# ArduBerry_V6_b.net
KiCad netlist of a schematic drawn in EAGLE
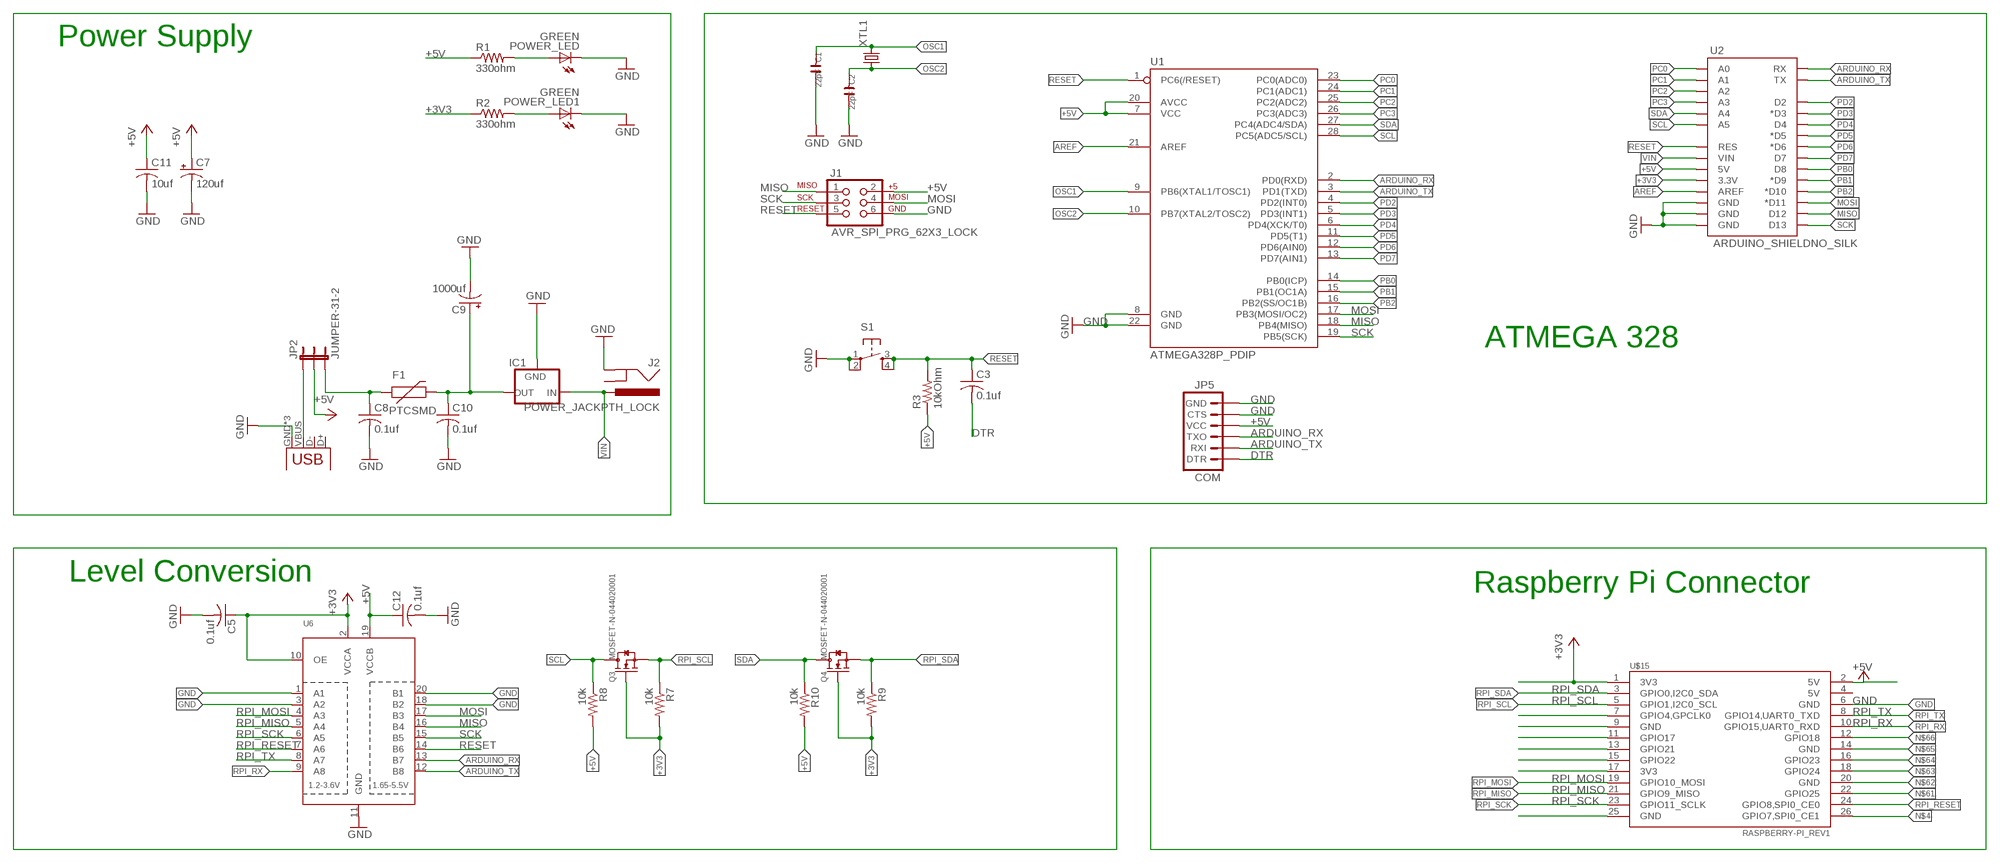
[diagram p0: schematic, sheet 1]

(export (version "E")
  (design (tool "Eeschema 10.0.6"))
  (components
    (comp (ref "C1")
      (value "22pF")
      (footprint "eagle-import:C0805")
      (libsource (lib "eagle-import") (part "C-0805"))
    )
    (comp (ref "C2")
      (value "22pF")
      (footprint "eagle-import:C0805")
      (libsource (lib "eagle-import") (part "C-0805"))
    )
    (comp (ref "C3")
      (value "0.1uf")
      (footprint "eagle-import:C0603")
      (libsource (lib "eagle-import") (part "resistor_C-USC0603"))
    )
    (comp (ref "C5")
      (value "0.1uf")
      (footprint "eagle-import:C0603")
      (libsource (lib "eagle-import") (part "resistor_C-USC0603"))
    )
    (comp (ref "C7")
      (value "120uf")
      (footprint "eagle-import:E2,5-6")
      (libsource (lib "eagle-import") (part "CPOL-USE2.5-6"))
    )
    (comp (ref "C8")
      (value "0.1uf")
      (footprint "eagle-import:C0603")
      (libsource (lib "eagle-import") (part "resistor_C-USC0603"))
    )
    (comp (ref "C9")
      (value "1000uf")
      (footprint "eagle-import:E3,5-10")
      (libsource (lib "eagle-import") (part "CPOL-USE3.5-10"))
    )
    (comp (ref "C10")
      (value "0.1uf")
      (footprint "eagle-import:C0603")
      (libsource (lib "eagle-import") (part "resistor_C-USC0603"))
    )
    (comp (ref "C11")
      (value "10uf")
      (footprint "eagle-import:C0805")
      (libsource (lib "eagle-import") (part "C-USC0805"))
    )
    (comp (ref "C12")
      (value "0.1uf")
      (footprint "eagle-import:C0603")
      (libsource (lib "eagle-import") (part "resistor_C-USC0603"))
    )
    (comp (ref "F1")
      (value "PTCSMD")
      (footprint "eagle-import:PTC-1206")
      (libsource (lib "eagle-import") (part "PTCSMD"))
    )
    (comp (ref "IC1")
      (value "V_REG_78XXSIDE")
      (footprint "eagle-import:78XXL")
      (libsource (lib "eagle-import") (part "V_REG_78XXSIDE"))
    )
    (comp (ref "J1")
      (value "AVR_SPI_PRG_62X3_LOCK")
      (footprint "eagle-import:2X3_LOCK")
      (libsource (lib "eagle-import") (part "AVR_SPI_PRG_62X3_LOCK"))
    )
    (comp (ref "J2")
      (value "POWER_JACKPTH_LOCK")
      (footprint "eagle-import:POWER_JACK_PTH_LOCK")
      (libsource (lib "eagle-import") (part "POWER_JACKPTH_LOCK"))
    )
    (comp (ref "JP1")
      (value "USB-MICROB")
      (footprint "eagle-import:USB-MICROB")
      (libsource (lib "eagle-import") (part "USB-MICROB"))
    )
    (comp (ref "JP2")
      (value "JUMPER-31-2")
      (footprint "eagle-import:SJ_3_PASTE1&2")
      (libsource (lib "eagle-import") (part "JUMPER-31-2"))
    )
    (comp (ref "JP5")
      (value "COM")
      (footprint "eagle-import:1X06")
      (libsource (lib "eagle-import") (part "ARDUINO_SERIAL_PROGRAMPTH"))
    )
    (comp (ref "POWER_LED")
      (value "GREEN")
      (footprint "eagle-import:LED-0603")
      (libsource (lib "eagle-import") (part "LED-GREEN0603"))
    )
    (comp (ref "POWER_LED1")
      (value "GREEN")
      (footprint "eagle-import:LED-0603")
      (libsource (lib "eagle-import") (part "LED-GREEN0603"))
    )
    (comp (ref "Q3")
      (value "MOSFET-N-044020001")
      (footprint "eagle-import:SOT23")
      (libsource (lib "eagle-import") (part "MOSFET-N-044020001"))
    )
    (comp (ref "Q4")
      (value "MOSFET-N-044020001")
      (footprint "eagle-import:SOT23")
      (libsource (lib "eagle-import") (part "MOSFET-N-044020001"))
    )
    (comp (ref "R1")
      (value "330ohm")
      (footprint "eagle-import:0603-RES")
      (libsource (lib "eagle-import") (part "RESISTOR0603"))
    )
    (comp (ref "R2")
      (value "330ohm")
      (footprint "eagle-import:0603-RES")
      (libsource (lib "eagle-import") (part "RESISTOR0603"))
    )
    (comp (ref "R3")
      (value "10kOhm")
      (footprint "eagle-import:0603-RES")
      (libsource (lib "eagle-import") (part "RESISTOR0603"))
    )
    (comp (ref "R7")
      (value "10k")
      (footprint "eagle-import:0603-RES")
      (libsource (lib "eagle-import") (part "RESISTOR0603"))
    )
    (comp (ref "R8")
      (value "10k")
      (footprint "eagle-import:0603-RES")
      (libsource (lib "eagle-import") (part "RESISTOR0603"))
    )
    (comp (ref "R9")
      (value "10k")
      (footprint "eagle-import:0603-RES")
      (libsource (lib "eagle-import") (part "RESISTOR0603"))
    )
    (comp (ref "R10")
      (value "10k")
      (footprint "eagle-import:0603-RES")
      (libsource (lib "eagle-import") (part "RESISTOR0603"))
    )
    (comp (ref "S1")
      (value "TAC_SWITCHPTH")
      (footprint "eagle-import:TACTILE-PTH")
      (libsource (lib "eagle-import") (part "TAC_SWITCHPTH"))
    )
    (comp (ref "U$15")
      (value "RASPBERRY-PI_REV1")
      (footprint "eagle-import:RASPBERRY-PI_REV1")
      (libsource (lib "eagle-import") (part "RASPBERRY-PI_REV1"))
    )
    (comp (ref "U1")
      (value "ATMEGA328P_PDIP")
      (footprint "eagle-import:DIL28-3")
      (libsource (lib "eagle-import") (part "ATMEGA328P_PDIP"))
    )
    (comp (ref "U2")
      (value "ARDUINO_SHIELDNO_SILK")
      (footprint "eagle-import:DUEMILANOVE_VIAS")
      (libsource (lib "eagle-import") (part "ARDUINO_SHIELDNO_SILK"))
    )
    (comp (ref "U6")
      (value "TXB0108PWR")
      (footprint "eagle-import:TSSOP20")
      (libsource (lib "eagle-import") (part "TXB0108PWR"))
    )
    (comp (ref "XTL1")
      (value "CRYSTALHC49S")
      (footprint "eagle-import:HC49_S")
      (libsource (lib "eagle-import") (part "CRYSTALHC49S"))
    )
  )
  (nets
    (net (code "1") (name "+3V3") (class "Default")
      (node (ref "C5") (pin "1") (pinfunction "1_1") (pintype "passive"))
      (node (ref "Q3") (pin "1") (pinfunction "G_1") (pintype "passive"))
      (node (ref "Q4") (pin "1") (pinfunction "G_1") (pintype "passive"))
      (node (ref "R2") (pin "1") (pinfunction "1_1") (pintype "passive"))
      (node (ref "R7") (pin "2") (pinfunction "2_2") (pintype "passive"))
      (node (ref "R9") (pin "2") (pinfunction "2_2") (pintype "passive"))
      (node (ref "U$15") (pin "1") (pinfunction "3V3_1") (pintype "bidirectional"))
      (node (ref "U2") (pin "3.3V") (pinfunction "3.3V_3.3V") (pintype "bidirectional"))
      (node (ref "U6") (pin "10") (pinfunction "OE_10") (pintype "bidirectional"))
      (node (ref "U6") (pin "2") (pinfunction "VCCA_2") (pintype "bidirectional"))
    )
    (net (code "2") (name "+5V") (class "Default")
      (node (ref "C11") (pin "1") (pinfunction "1_1") (pintype "passive"))
      (node (ref "C12") (pin "1") (pinfunction "1_1") (pintype "passive"))
      (node (ref "C7") (pin "+") (pinfunction "+_+") (pintype "passive"))
      (node (ref "J1") (pin "2") (pinfunction "2_2") (pintype "passive"))
      (node (ref "JP2") (pin "2") (pinfunction "2_2") (pintype "passive"))
      (node (ref "JP5") (pin "4") (pinfunction "VCC_4") (pintype "passive"))
      (node (ref "R1") (pin "1") (pinfunction "1_1") (pintype "passive"))
      (node (ref "R10") (pin "2") (pinfunction "2_2") (pintype "passive"))
      (node (ref "R3") (pin "1") (pinfunction "1_1") (pintype "passive"))
      (node (ref "R8") (pin "2") (pinfunction "2_2") (pintype "passive"))
      (node (ref "U$15") (pin "2") (pinfunction "5V_2") (pintype "bidirectional"))
      (node (ref "U1") (pin "20") (pinfunction "AVCC_20") (pintype "bidirectional"))
      (node (ref "U1") (pin "7") (pinfunction "VCC_7") (pintype "bidirectional"))
      (node (ref "U2") (pin "5V") (pinfunction "5V_5V") (pintype "bidirectional"))
      (node (ref "U6") (pin "19") (pinfunction "VCCB_19") (pintype "bidirectional"))
    )
    (net (code "3") (name "/DTR") (class "Default")
      (node (ref "C3") (pin "2") (pinfunction "2_2") (pintype "passive"))
      (node (ref "JP5") (pin "1") (pinfunction "DTR_1") (pintype "passive"))
    )
    (net (code "4") (name "ARDUINO_RX") (class "Default")
      (node (ref "JP5") (pin "3") (pinfunction "TXO_3") (pintype "passive"))
      (node (ref "U1") (pin "2") (pinfunction "PD0(RXD)_2") (pintype "bidirectional"))
      (node (ref "U2") (pin "RX") (pinfunction "RX_RX") (pintype "bidirectional"))
      (node (ref "U6") (pin "13") (pinfunction "B7_13") (pintype "bidirectional"))
    )
    (net (code "5") (name "ARDUINO_TX") (class "Default")
      (node (ref "JP5") (pin "2") (pinfunction "RXI_2") (pintype "passive"))
      (node (ref "U1") (pin "3") (pinfunction "PD1(TXD)_3") (pintype "bidirectional"))
      (node (ref "U2") (pin "TX") (pinfunction "TX_TX") (pintype "bidirectional"))
      (node (ref "U6") (pin "12") (pinfunction "B8_12") (pintype "bidirectional"))
    )
    (net (code "6") (name "AREF") (class "Default")
      (node (ref "U1") (pin "21") (pinfunction "AREF_21") (pintype "bidirectional"))
      (node (ref "U2") (pin "AREF") (pinfunction "AREF_AREF") (pintype "bidirectional"))
    )
    (net (code "7") (name "GND") (class "Default")
      (node (ref "C1") (pin "2") (pinfunction "2_2") (pintype "bidirectional"))
      (node (ref "C10") (pin "2") (pinfunction "2_2") (pintype "passive"))
      (node (ref "C11") (pin "2") (pinfunction "2_2") (pintype "passive"))
      (node (ref "C12") (pin "2") (pinfunction "2_2") (pintype "passive"))
      (node (ref "C2") (pin "2") (pinfunction "2_2") (pintype "bidirectional"))
      (node (ref "C5") (pin "2") (pinfunction "2_2") (pintype "passive"))
      (node (ref "C7") (pin "-") (pinfunction "-_-") (pintype "passive"))
      (node (ref "C8") (pin "2") (pinfunction "2_2") (pintype "passive"))
      (node (ref "C9") (pin "-") (pinfunction "-_-") (pintype "passive"))
      (node (ref "IC1") (pin "GND") (pinfunction "GND_GND") (pintype "input"))
      (node (ref "J1") (pin "6") (pinfunction "6_6") (pintype "passive"))
      (node (ref "J2") (pin "GND") (pinfunction "GND_GND") (pintype "bidirectional"))
      (node (ref "JP1") (pin "GND") (pinfunction "GND_GND") (pintype "bidirectional"))
      (node (ref "JP1") (pin "MT1") (pinfunction "GND_MT1") (pintype "bidirectional"))
      (node (ref "JP1") (pin "MT2") (pinfunction "GND_MT2") (pintype "bidirectional"))
      (node (ref "JP5") (pin "5") (pinfunction "CTS_5") (pintype "passive"))
      (node (ref "JP5") (pin "6") (pinfunction "GND_6") (pintype "passive"))
      (node (ref "POWER_LED") (pin "C") (pinfunction "C_C") (pintype "passive"))
      (node (ref "POWER_LED1") (pin "C") (pinfunction "C_C") (pintype "passive"))
      (node (ref "S1") (pin "1") (pinfunction "1_1") (pintype "passive"))
      (node (ref "S1") (pin "2") (pinfunction "2_2") (pintype "passive"))
      (node (ref "U$15") (pin "6") (pinfunction "GND_6") (pintype "bidirectional"))
      (node (ref "U1") (pin "22") (pinfunction "GND_22") (pintype "bidirectional"))
      (node (ref "U1") (pin "8") (pinfunction "GND_8") (pintype "bidirectional"))
      (node (ref "U2") (pin "GND@0") (pinfunction "GND_GND@0") (pintype "bidirectional"))
      (node (ref "U2") (pin "GND@1") (pinfunction "GND_GND@1") (pintype "bidirectional"))
      (node (ref "U2") (pin "GND@2") (pinfunction "GND_GND@2") (pintype "bidirectional"))
      (node (ref "U6") (pin "1") (pinfunction "A1_1") (pintype "bidirectional"))
      (node (ref "U6") (pin "11") (pinfunction "GND_11") (pintype "bidirectional"))
      (node (ref "U6") (pin "18") (pinfunction "B2_18") (pintype "bidirectional"))
      (node (ref "U6") (pin "20") (pinfunction "B1_20") (pintype "bidirectional"))
      (node (ref "U6") (pin "3") (pinfunction "A2_3") (pintype "bidirectional"))
    )
    (net (code "8") (name "MISO") (class "Default")
      (node (ref "J1") (pin "1") (pinfunction "1_1") (pintype "passive"))
      (node (ref "U1") (pin "18") (pinfunction "PB4(MISO)_18") (pintype "bidirectional"))
      (node (ref "U2") (pin "D12") (pinfunction "D12_D12") (pintype "bidirectional"))
      (node (ref "U6") (pin "16") (pinfunction "B4_16") (pintype "bidirectional"))
    )
    (net (code "9") (name "MOSI") (class "Default")
      (node (ref "J1") (pin "4") (pinfunction "4_4") (pintype "passive"))
      (node (ref "U1") (pin "17") (pinfunction "PB3(MOSI/OC2)_17") (pintype "bidirectional"))
      (node (ref "U2") (pin "D11") (pinfunction "*D11_D11") (pintype "bidirectional"))
      (node (ref "U6") (pin "17") (pinfunction "B3_17") (pintype "bidirectional"))
    )
    (net (code "10") (name "N$4") (class "Default")
      (node (ref "U$15") (pin "26") (pinfunction "GPIO7,SPI0_CE1_26") (pintype "bidirectional"))
    )
    (net (code "11") (name "N$61") (class "Default")
      (node (ref "U$15") (pin "22") (pinfunction "GPIO25_22") (pintype "bidirectional"))
    )
    (net (code "12") (name "N$62") (class "Default")
      (node (ref "U$15") (pin "20") (pinfunction "GND_20") (pintype "bidirectional"))
    )
    (net (code "13") (name "N$63") (class "Default")
      (node (ref "U$15") (pin "18") (pinfunction "GPIO24_18") (pintype "bidirectional"))
    )
    (net (code "14") (name "N$64") (class "Default")
      (node (ref "U$15") (pin "16") (pinfunction "GPIO23_16") (pintype "bidirectional"))
    )
    (net (code "15") (name "N$65") (class "Default")
      (node (ref "U$15") (pin "14") (pinfunction "GND_14") (pintype "bidirectional"))
    )
    (net (code "16") (name "N$66") (class "Default")
      (node (ref "U$15") (pin "12") (pinfunction "GPIO18_12") (pintype "bidirectional"))
    )
    (net (code "17") (name "Net-(C8-Pad1)") (class "Default")
      (node (ref "C8") (pin "1") (pinfunction "1_1") (pintype "passive"))
      (node (ref "F1") (pin "1") (pinfunction "1_1") (pintype "bidirectional"))
      (node (ref "JP2") (pin "3") (pinfunction "3_3") (pintype "passive"))
    )
    (net (code "18") (name "Net-(C10-Pad1)") (class "Default")
      (node (ref "C10") (pin "1") (pinfunction "1_1") (pintype "passive"))
      (node (ref "C9") (pin "+") (pinfunction "+_+") (pintype "passive"))
      (node (ref "F1") (pin "2") (pinfunction "2_2") (pintype "bidirectional"))
      (node (ref "IC1") (pin "OUT") (pinfunction "OUT_OUT") (pintype "output"))
    )
    (net (code "19") (name "Net-(JP1-PadVBUS)") (class "Default")
      (node (ref "JP1") (pin "VBUS") (pinfunction "VBUS_VBUS") (pintype "bidirectional"))
      (node (ref "JP2") (pin "1") (pinfunction "1_1") (pintype "passive"))
    )
    (net (code "20") (name "Net-(POWER_LED-PadA)") (class "Default")
      (node (ref "POWER_LED") (pin "A") (pinfunction "A_A") (pintype "passive"))
      (node (ref "R1") (pin "2") (pinfunction "2_2") (pintype "passive"))
    )
    (net (code "21") (name "Net-(POWER_LED1-PadA)") (class "Default")
      (node (ref "POWER_LED1") (pin "A") (pinfunction "A_A") (pintype "passive"))
      (node (ref "R2") (pin "2") (pinfunction "2_2") (pintype "passive"))
    )
    (net (code "22") (name "OSC1") (class "Default")
      (node (ref "C1") (pin "1") (pinfunction "1_1") (pintype "bidirectional"))
      (node (ref "U1") (pin "9") (pinfunction "PB6(XTAL1/TOSC1)_9") (pintype "bidirectional"))
      (node (ref "XTL1") (pin "2") (pinfunction "2_2") (pintype "passive"))
    )
    (net (code "23") (name "OSC2") (class "Default")
      (node (ref "C2") (pin "1") (pinfunction "1_1") (pintype "bidirectional"))
      (node (ref "U1") (pin "10") (pinfunction "PB7(XTAL2/TOSC2)_10") (pintype "bidirectional"))
      (node (ref "XTL1") (pin "1") (pinfunction "1_1") (pintype "passive"))
    )
    (net (code "24") (name "PB0") (class "Default")
      (node (ref "U1") (pin "14") (pinfunction "PB0(ICP)_14") (pintype "bidirectional"))
      (node (ref "U2") (pin "D8") (pinfunction "D8_D8") (pintype "bidirectional"))
    )
    (net (code "25") (name "PB1") (class "Default")
      (node (ref "U1") (pin "15") (pinfunction "PB1(OC1A)_15") (pintype "bidirectional"))
      (node (ref "U2") (pin "D9") (pinfunction "*D9_D9") (pintype "bidirectional"))
    )
    (net (code "26") (name "PB2") (class "Default")
      (node (ref "U1") (pin "16") (pinfunction "PB2(SS/OC1B)_16") (pintype "bidirectional"))
      (node (ref "U2") (pin "D10") (pinfunction "*D10_D10") (pintype "bidirectional"))
    )
    (net (code "27") (name "PC0") (class "Default")
      (node (ref "U1") (pin "23") (pinfunction "PC0(ADC0)_23") (pintype "bidirectional"))
      (node (ref "U2") (pin "A0") (pinfunction "A0_A0") (pintype "bidirectional"))
    )
    (net (code "28") (name "PC1") (class "Default")
      (node (ref "U1") (pin "24") (pinfunction "PC1(ADC1)_24") (pintype "bidirectional"))
      (node (ref "U2") (pin "A1") (pinfunction "A1_A1") (pintype "bidirectional"))
    )
    (net (code "29") (name "PC2") (class "Default")
      (node (ref "U1") (pin "25") (pinfunction "PC2(ADC2)_25") (pintype "bidirectional"))
      (node (ref "U2") (pin "A2") (pinfunction "A2_A2") (pintype "bidirectional"))
    )
    (net (code "30") (name "PC3") (class "Default")
      (node (ref "U1") (pin "26") (pinfunction "PC3(ADC3)_26") (pintype "bidirectional"))
      (node (ref "U2") (pin "A3") (pinfunction "A3_A3") (pintype "bidirectional"))
    )
    (net (code "31") (name "PD2") (class "Default")
      (node (ref "U1") (pin "4") (pinfunction "PD2(INT0)_4") (pintype "bidirectional"))
      (node (ref "U2") (pin "D2") (pinfunction "D2_D2") (pintype "bidirectional"))
    )
    (net (code "32") (name "PD3") (class "Default")
      (node (ref "U1") (pin "5") (pinfunction "PD3(INT1)_5") (pintype "bidirectional"))
      (node (ref "U2") (pin "D3") (pinfunction "*D3_D3") (pintype "bidirectional"))
    )
    (net (code "33") (name "PD4") (class "Default")
      (node (ref "U1") (pin "6") (pinfunction "PD4(XCK/T0)_6") (pintype "bidirectional"))
      (node (ref "U2") (pin "D4") (pinfunction "D4_D4") (pintype "bidirectional"))
    )
    (net (code "34") (name "PD5") (class "Default")
      (node (ref "U1") (pin "11") (pinfunction "PD5(T1)_11") (pintype "bidirectional"))
      (node (ref "U2") (pin "D5") (pinfunction "*D5_D5") (pintype "bidirectional"))
    )
    (net (code "35") (name "PD6") (class "Default")
      (node (ref "U1") (pin "12") (pinfunction "PD6(AIN0)_12") (pintype "bidirectional"))
      (node (ref "U2") (pin "D6") (pinfunction "*D6_D6") (pintype "bidirectional"))
    )
    (net (code "36") (name "PD7") (class "Default")
      (node (ref "U1") (pin "13") (pinfunction "PD7(AIN1)_13") (pintype "bidirectional"))
      (node (ref "U2") (pin "D7") (pinfunction "D7_D7") (pintype "bidirectional"))
    )
    (net (code "37") (name "RESET") (class "Default")
      (node (ref "C3") (pin "1") (pinfunction "1_1") (pintype "passive"))
      (node (ref "J1") (pin "5") (pinfunction "5_5") (pintype "passive"))
      (node (ref "R3") (pin "2") (pinfunction "2_2") (pintype "passive"))
      (node (ref "S1") (pin "3") (pinfunction "3_3") (pintype "passive"))
      (node (ref "S1") (pin "4") (pinfunction "4_4") (pintype "passive"))
      (node (ref "U1") (pin "1") (pinfunction "PC6(/RESET)_1") (pintype "bidirectional"))
      (node (ref "U2") (pin "RES") (pinfunction "RES_RES") (pintype "bidirectional"))
      (node (ref "U6") (pin "14") (pinfunction "B6_14") (pintype "bidirectional"))
    )
    (net (code "38") (name "RPI_MISO") (class "Default")
      (node (ref "U$15") (pin "21") (pinfunction "GPIO9_MISO_21") (pintype "bidirectional"))
      (node (ref "U6") (pin "5") (pinfunction "A4_5") (pintype "bidirectional"))
    )
    (net (code "39") (name "RPI_MOSI") (class "Default")
      (node (ref "U$15") (pin "19") (pinfunction "GPIO10_MOSI_19") (pintype "bidirectional"))
      (node (ref "U6") (pin "4") (pinfunction "A3_4") (pintype "bidirectional"))
    )
    (net (code "40") (name "RPI_RESET") (class "Default")
      (node (ref "U$15") (pin "24") (pinfunction "GPIO8,SPI0_CE0_24") (pintype "bidirectional"))
      (node (ref "U6") (pin "7") (pinfunction "A6_7") (pintype "bidirectional"))
    )
    (net (code "41") (name "RPI_RX") (class "Default")
      (node (ref "U$15") (pin "10") (pinfunction "GPIO15,UART0_RXD_10") (pintype "bidirectional"))
      (node (ref "U6") (pin "9") (pinfunction "A8_9") (pintype "bidirectional"))
    )
    (net (code "42") (name "RPI_SCK") (class "Default")
      (node (ref "U$15") (pin "23") (pinfunction "GPIO11_SCLK_23") (pintype "bidirectional"))
      (node (ref "U6") (pin "6") (pinfunction "A5_6") (pintype "bidirectional"))
    )
    (net (code "43") (name "RPI_SCL") (class "Default")
      (node (ref "Q3") (pin "2") (pinfunction "S_2") (pintype "passive"))
      (node (ref "R7") (pin "1") (pinfunction "1_1") (pintype "passive"))
      (node (ref "U$15") (pin "5") (pinfunction "GPIO1,I2C0_SCL_5") (pintype "bidirectional"))
    )
    (net (code "44") (name "RPI_SDA") (class "Default")
      (node (ref "Q4") (pin "2") (pinfunction "S_2") (pintype "passive"))
      (node (ref "R9") (pin "1") (pinfunction "1_1") (pintype "passive"))
      (node (ref "U$15") (pin "3") (pinfunction "GPIO0,I2C0_SDA_3") (pintype "bidirectional"))
    )
    (net (code "45") (name "RPI_TX") (class "Default")
      (node (ref "U$15") (pin "8") (pinfunction "GPIO14,UART0_TXD_8") (pintype "bidirectional"))
      (node (ref "U6") (pin "8") (pinfunction "A7_8") (pintype "bidirectional"))
    )
    (net (code "46") (name "SCK") (class "Default")
      (node (ref "J1") (pin "3") (pinfunction "3_3") (pintype "passive"))
      (node (ref "U1") (pin "19") (pinfunction "PB5(SCK)_19") (pintype "bidirectional"))
      (node (ref "U2") (pin "D13") (pinfunction "D13_D13") (pintype "bidirectional"))
      (node (ref "U6") (pin "15") (pinfunction "B5_15") (pintype "bidirectional"))
    )
    (net (code "47") (name "SCL") (class "Default")
      (node (ref "Q3") (pin "3") (pinfunction "D_3") (pintype "passive"))
      (node (ref "R8") (pin "1") (pinfunction "1_1") (pintype "passive"))
      (node (ref "U1") (pin "28") (pinfunction "PC5(ADC5/SCL)_28") (pintype "bidirectional"))
      (node (ref "U2") (pin "A5") (pinfunction "A5_A5") (pintype "bidirectional"))
    )
    (net (code "48") (name "SDA") (class "Default")
      (node (ref "Q4") (pin "3") (pinfunction "D_3") (pintype "passive"))
      (node (ref "R10") (pin "1") (pinfunction "1_1") (pintype "passive"))
      (node (ref "U1") (pin "27") (pinfunction "PC4(ADC4/SDA)_27") (pintype "bidirectional"))
      (node (ref "U2") (pin "A4") (pinfunction "A4_A4") (pintype "bidirectional"))
    )
    (net (code "49") (name "VIN") (class "Default")
      (node (ref "IC1") (pin "IN") (pinfunction "IN_IN") (pintype "input"))
      (node (ref "J2") (pin "PWR") (pinfunction "PWR_PWR") (pintype "bidirectional"))
      (node (ref "U2") (pin "VIN") (pinfunction "VIN_VIN") (pintype "bidirectional"))
    )
    (net (code "50") (name "unconnected-(J2-PadGNDBREAK)") (class "Default")
      (node (ref "J2") (pin "GNDBREAK") (pinfunction "GNDBREAK_GNDBREAK") (pintype "bidirectional"))
    )
    (net (code "51") (name "unconnected-(JP1-PadD+)") (class "Default")
      (node (ref "JP1") (pin "D+") (pinfunction "D+_D+") (pintype "bidirectional"))
    )
    (net (code "52") (name "unconnected-(JP1-PadD-)") (class "Default")
      (node (ref "JP1") (pin "D-") (pinfunction "D-_D-") (pintype "bidirectional"))
    )
    (net (code "53") (name "unconnected-(U$15-3V3-Pad17)") (class "Default")
      (node (ref "U$15") (pin "17") (pinfunction "3V3_17") (pintype "bidirectional"))
    )
    (net (code "54") (name "unconnected-(U$15-5V-Pad4)") (class "Default")
      (node (ref "U$15") (pin "4") (pinfunction "5V_4") (pintype "bidirectional"))
    )
    (net (code "55") (name "unconnected-(U$15-GND-Pad9)") (class "Default")
      (node (ref "U$15") (pin "9") (pinfunction "GND_9") (pintype "bidirectional"))
    )
    (net (code "56") (name "unconnected-(U$15-GND-Pad25)") (class "Default")
      (node (ref "U$15") (pin "25") (pinfunction "GND_25") (pintype "bidirectional"))
    )
    (net (code "57") (name "unconnected-(U$15-GPIO4,GPCLK0-Pad7)") (class "Default")
      (node (ref "U$15") (pin "7") (pinfunction "GPIO4,GPCLK0_7") (pintype "bidirectional"))
    )
    (net (code "58") (name "unconnected-(U$15-GPIO17-Pad11)") (class "Default")
      (node (ref "U$15") (pin "11") (pinfunction "GPIO17_11") (pintype "bidirectional"))
    )
    (net (code "59") (name "unconnected-(U$15-GPIO21-Pad13)") (class "Default")
      (node (ref "U$15") (pin "13") (pinfunction "GPIO21_13") (pintype "bidirectional"))
    )
    (net (code "60") (name "unconnected-(U$15-GPIO22-Pad15)") (class "Default")
      (node (ref "U$15") (pin "15") (pinfunction "GPIO22_15") (pintype "bidirectional"))
    )
  )
)
